# PowerSwitch.net
KiCad netlist of a schematic drawn in Altium Designer
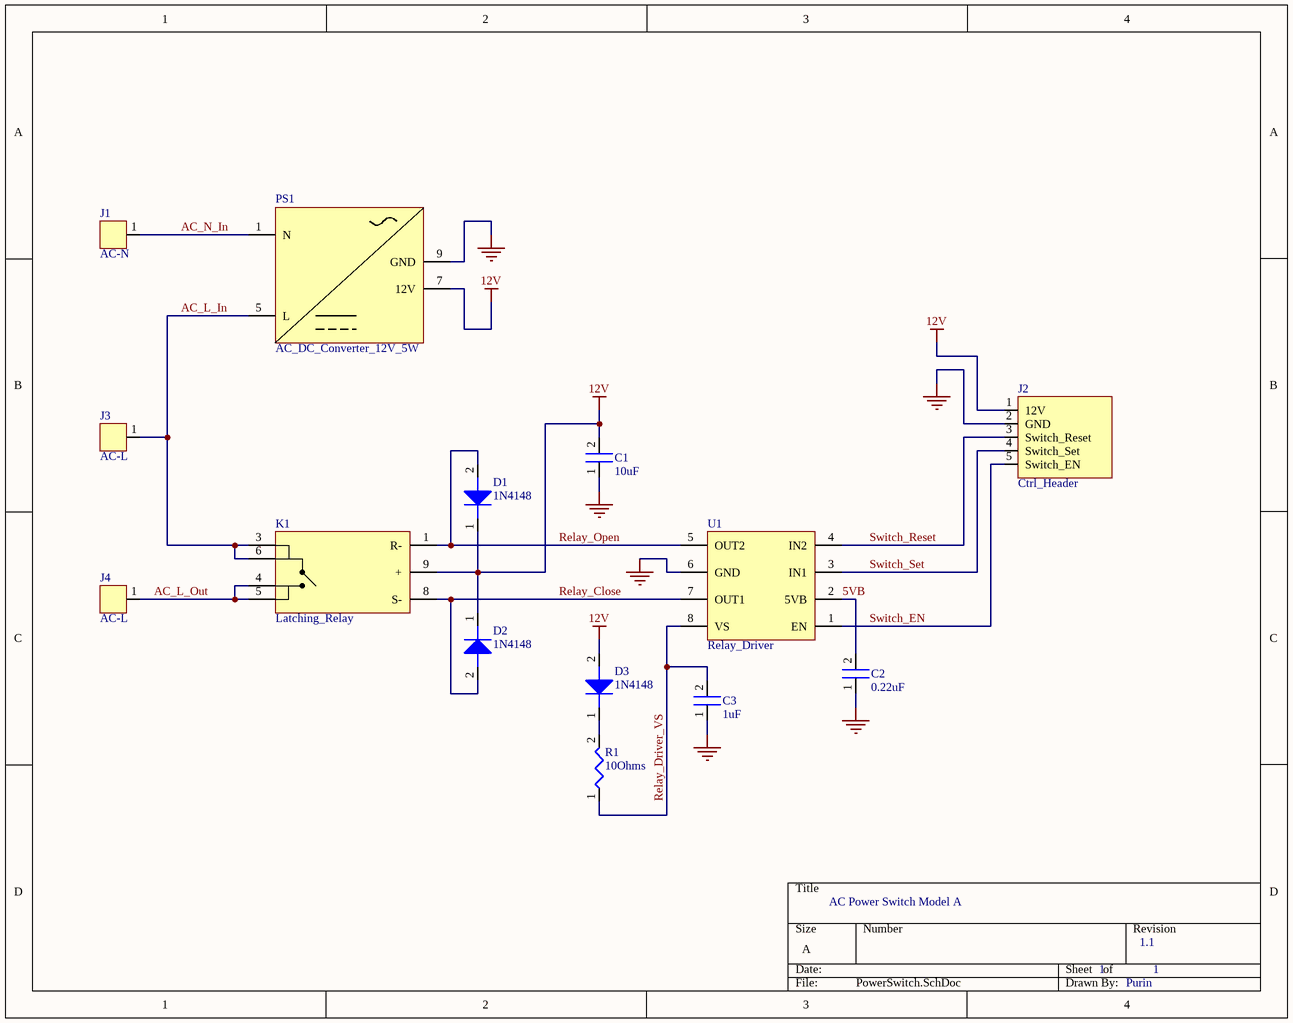
[diagram p0: PowerSwitch.SchDoc]

(export (version "E")
  (design (tool "Eeschema 10.0.6"))
  (components
    (comp (ref "C1")
      (value "10uF")
      (footprint "C0805")
      (description "10µF ±10% 16V Ceramic Capacitor X7R 0805 (2012 Metric)")
      (fields
        (field (name "MANUFACTURER") "Samsung")
        (field (name "MANUFACTURER PART NUMBER") "CL21B106KOQNNNE")
      )
      (libsource (lib "altium-import") (part "root_1_CL21B106KOQNNNE_"))
    )
    (comp (ref "C2")
      (value "0.22uF")
      (footprint "C0805")
      (description "0.22µF ±10% 50V Ceramic Capacitor X7R 0805 (2012 Metric)")
      (fields
        (field (name "MANUFACTURER") "TDK")
        (field (name "MANUFACTURER PART NUMBER") "CGA4J2X7R1H224K125AE")
      )
      (libsource (lib "altium-import") (part "root_1_CGA4J2X7R1H224K125AE_"))
    )
    (comp (ref "C3")
      (value "1uF")
      (footprint "C0805")
      (description "1µF ±10% 35V Ceramic Capacitor X7R 0805 (2012 Metric)")
      (fields
        (field (name "MANUFACTURER") "TDK")
        (field (name "MANUFACTURER PART NUMBER") "CGA4J3X7R1V105K125AB")
      )
      (libsource (lib "altium-import") (part "root_1_CGA4J3X7R1V105K125AB_"))
    )
    (comp (ref "D1")
      (value "1N4148")
      (footprint "1N4148SOD123")
      (description "Small Signal Diode, Single, 100 V, 300 Ma, 1.25 V, 4 Ns, 2 A Rohs Compliant: Yes")
      (fields
        (field (name "MANUFACTURER") "Diodes Inc.")
        (field (name "MANUFACTURER PART NUMBER") "1N4148W-7-F")
      )
      (libsource (lib "altium-import") (part "root_1_1N4148W-7-F_"))
    )
    (comp (ref "D2")
      (value "1N4148")
      (footprint "1N4148SOD123")
      (description "Small Signal Diode, Single, 100 V, 300 Ma, 1.25 V, 4 Ns, 2 A Rohs Compliant: Yes")
      (fields
        (field (name "MANUFACTURER") "Diodes Inc.")
        (field (name "MANUFACTURER PART NUMBER") "1N4148W-7-F")
      )
      (libsource (lib "altium-import") (part "root_3_1N4148W-7-F_"))
    )
    (comp (ref "D3")
      (value "1N4148")
      (footprint "1N4148SOD123")
      (description "Small Signal Diode, Single, 100 V, 300 Ma, 1.25 V, 4 Ns, 2 A Rohs Compliant: Yes")
      (fields
        (field (name "MANUFACTURER") "Diodes Inc.")
        (field (name "MANUFACTURER PART NUMBER") "1N4148W-7-F")
      )
      (libsource (lib "altium-import") (part "root_1_1N4148W-7-F_"))
    )
    (comp (ref "J1")
      (value "AC-N")
      (footprint "AC-HEADER")
      (libsource (lib "altium-import") (part "root_0_AC-N-Header_"))
    )
    (comp (ref "J2")
      (value "Ctrl_Header")
      (footprint "CTRL-HEADER")
      (libsource (lib "Power_Switch_SchLib") (part "Ctrl-Header"))
    )
    (comp (ref "J3")
      (value "AC-L")
      (footprint "AC-HEADER")
      (libsource (lib "altium-import") (part "root_0_AC-L-Header_"))
    )
    (comp (ref "J4")
      (value "AC-L")
      (footprint "AC-HEADER")
      (libsource (lib "altium-import") (part "root_0_AC-L-Header_"))
    )
    (comp (ref "K1")
      (value "Latching_Relay")
      (footprint "G5RL-K1A-E")
      (description "General Purpose Relay, G5rl-K Series, Power, Latching Dual Coil, Spst-No, 12 Vdc, 16 A")
      (fields
        (field (name "MANUFACTURER") "Omron")
        (field (name "MANUFACTURER PART NUMBER") "G5RL-K1A-E-DC12")
      )
      (libsource (lib "Power_Switch_SchLib") (part "G5RL-K1A-E-DC12"))
    )
    (comp (ref "PS1")
      (value "AC_DC_Converter_12V_5W")
      (footprint "RAC05-K/277")
      (description "Enclosed AC DC Converter 1 Output 12V    416mA 85 ~ 305 VAC, 120 ~ 430 VDC Input")
      (fields
        (field (name "MANUFACTURER") "Recom Power")
        (field (name "MANUFACTURER PART NUMBER") "RAC05-12SK/277")
      )
      (libsource (lib "Power_Switch_SchLib") (part "RAC05-12SK/277"))
    )
    (comp (ref "R1")
      (value "10Ohms")
      (footprint "R0805")
      (description "10 Ohms ±1% 0.125W, 1/8W Chip Resistor 0805 (2012 Metric)  Thick Film")
      (fields
        (field (name "MANUFACTURER") "Vishay")
        (field (name "MANUFACTURER PART NUMBER") "CRCW080510R0FKEAC")
      )
      (libsource (lib "altium-import") (part "root_1_CRCW080510R0FKEAC_"))
    )
    (comp (ref "U1")
      (value "Relay_Driver")
      (footprint "FAN324X")
      (description "FAN3240TMX, Dual-Channel Latching Relay Driver")
      (fields
        (field (name "MANUFACTURER") "ON Semiconductor")
        (field (name "MANUFACTURER PART NUMBER") "FAN3240TMX")
      )
      (libsource (lib "Power_Switch_SchLib") (part "FAN3240TMX"))
    )
  )
  (nets
    (net (code "1") (name "/5VB") (class "Default")
      (node (ref "C2") (pin "2") (pinfunction "2_2") (pintype "passive"))
      (node (ref "U1") (pin "2") (pinfunction "5VB_2") (pintype "passive"))
    )
    (net (code "2") (name "/AC_L_In") (class "Default")
      (node (ref "J3") (pin "1") (pinfunction "L_1") (pintype "passive"))
      (node (ref "K1") (pin "3") (pinfunction "3_3") (pintype "passive"))
      (node (ref "K1") (pin "6") (pinfunction "6_6") (pintype "passive"))
      (node (ref "PS1") (pin "5") (pinfunction "L_5") (pintype "passive"))
    )
    (net (code "3") (name "/AC_L_Out") (class "Default")
      (node (ref "J4") (pin "1") (pinfunction "L_1") (pintype "passive"))
      (node (ref "K1") (pin "4") (pinfunction "4_4") (pintype "passive"))
      (node (ref "K1") (pin "5") (pinfunction "5_5") (pintype "passive"))
    )
    (net (code "4") (name "/AC_N_In") (class "Default")
      (node (ref "J1") (pin "1") (pinfunction "N_1") (pintype "passive"))
      (node (ref "PS1") (pin "1") (pinfunction "N_1") (pintype "passive"))
    )
    (net (code "5") (name "/Relay_Close") (class "Default")
      (node (ref "D2") (pin "2") (pinfunction "2_2") (pintype "passive"))
      (node (ref "K1") (pin "8") (pinfunction "S-_8") (pintype "passive"))
      (node (ref "U1") (pin "7") (pinfunction "OUT1_7") (pintype "passive"))
    )
    (net (code "6") (name "/Relay_Driver_VS") (class "Default")
      (node (ref "C3") (pin "2") (pinfunction "2_2") (pintype "passive"))
      (node (ref "R1") (pin "1") (pinfunction "1_1") (pintype "passive"))
      (node (ref "U1") (pin "8") (pinfunction "VS_8") (pintype "passive"))
    )
    (net (code "7") (name "/Relay_Open") (class "Default")
      (node (ref "D1") (pin "2") (pinfunction "2_2") (pintype "passive"))
      (node (ref "K1") (pin "1") (pinfunction "R-_1") (pintype "passive"))
      (node (ref "U1") (pin "5") (pinfunction "OUT2_5") (pintype "passive"))
    )
    (net (code "8") (name "/Switch_EN") (class "Default")
      (node (ref "J2") (pin "5") (pinfunction "Switch_EN_5") (pintype "passive"))
      (node (ref "U1") (pin "1") (pinfunction "EN_1") (pintype "passive"))
    )
    (net (code "9") (name "/Switch_Reset") (class "Default")
      (node (ref "J2") (pin "3") (pinfunction "Switch_Reset_3") (pintype "passive"))
      (node (ref "U1") (pin "4") (pinfunction "IN2_4") (pintype "passive"))
    )
    (net (code "10") (name "/Switch_Set") (class "Default")
      (node (ref "J2") (pin "4") (pinfunction "Switch_Set_4") (pintype "passive"))
      (node (ref "U1") (pin "3") (pinfunction "IN1_3") (pintype "passive"))
    )
    (net (code "11") (name "12V") (class "Default")
      (node (ref "C1") (pin "2") (pinfunction "2_2") (pintype "passive"))
      (node (ref "D1") (pin "1") (pinfunction "1_1") (pintype "passive"))
      (node (ref "D2") (pin "1") (pinfunction "1_1") (pintype "passive"))
      (node (ref "D3") (pin "2") (pinfunction "2_2") (pintype "passive"))
      (node (ref "J2") (pin "1") (pinfunction "12V_1") (pintype "passive"))
      (node (ref "K1") (pin "9") (pinfunction "+_9") (pintype "passive"))
      (node (ref "PS1") (pin "7") (pinfunction "12V_7") (pintype "passive"))
    )
    (net (code "12") (name "GND") (class "Default")
      (node (ref "C1") (pin "1") (pinfunction "1_1") (pintype "passive"))
      (node (ref "C2") (pin "1") (pinfunction "1_1") (pintype "passive"))
      (node (ref "C3") (pin "1") (pinfunction "1_1") (pintype "passive"))
      (node (ref "J2") (pin "2") (pinfunction "GND_2") (pintype "passive"))
      (node (ref "PS1") (pin "9") (pinfunction "GND_9") (pintype "passive"))
      (node (ref "U1") (pin "6") (pinfunction "GND_6") (pintype "passive"))
    )
    (net (code "13") (name "Net-(D3-Pad1)") (class "Default")
      (node (ref "D3") (pin "1") (pinfunction "1_1") (pintype "passive"))
      (node (ref "R1") (pin "2") (pinfunction "2_2") (pintype "passive"))
    )
  )
)
